# Sheet2.net
KiCad netlist of a schematic drawn in Altium Designer
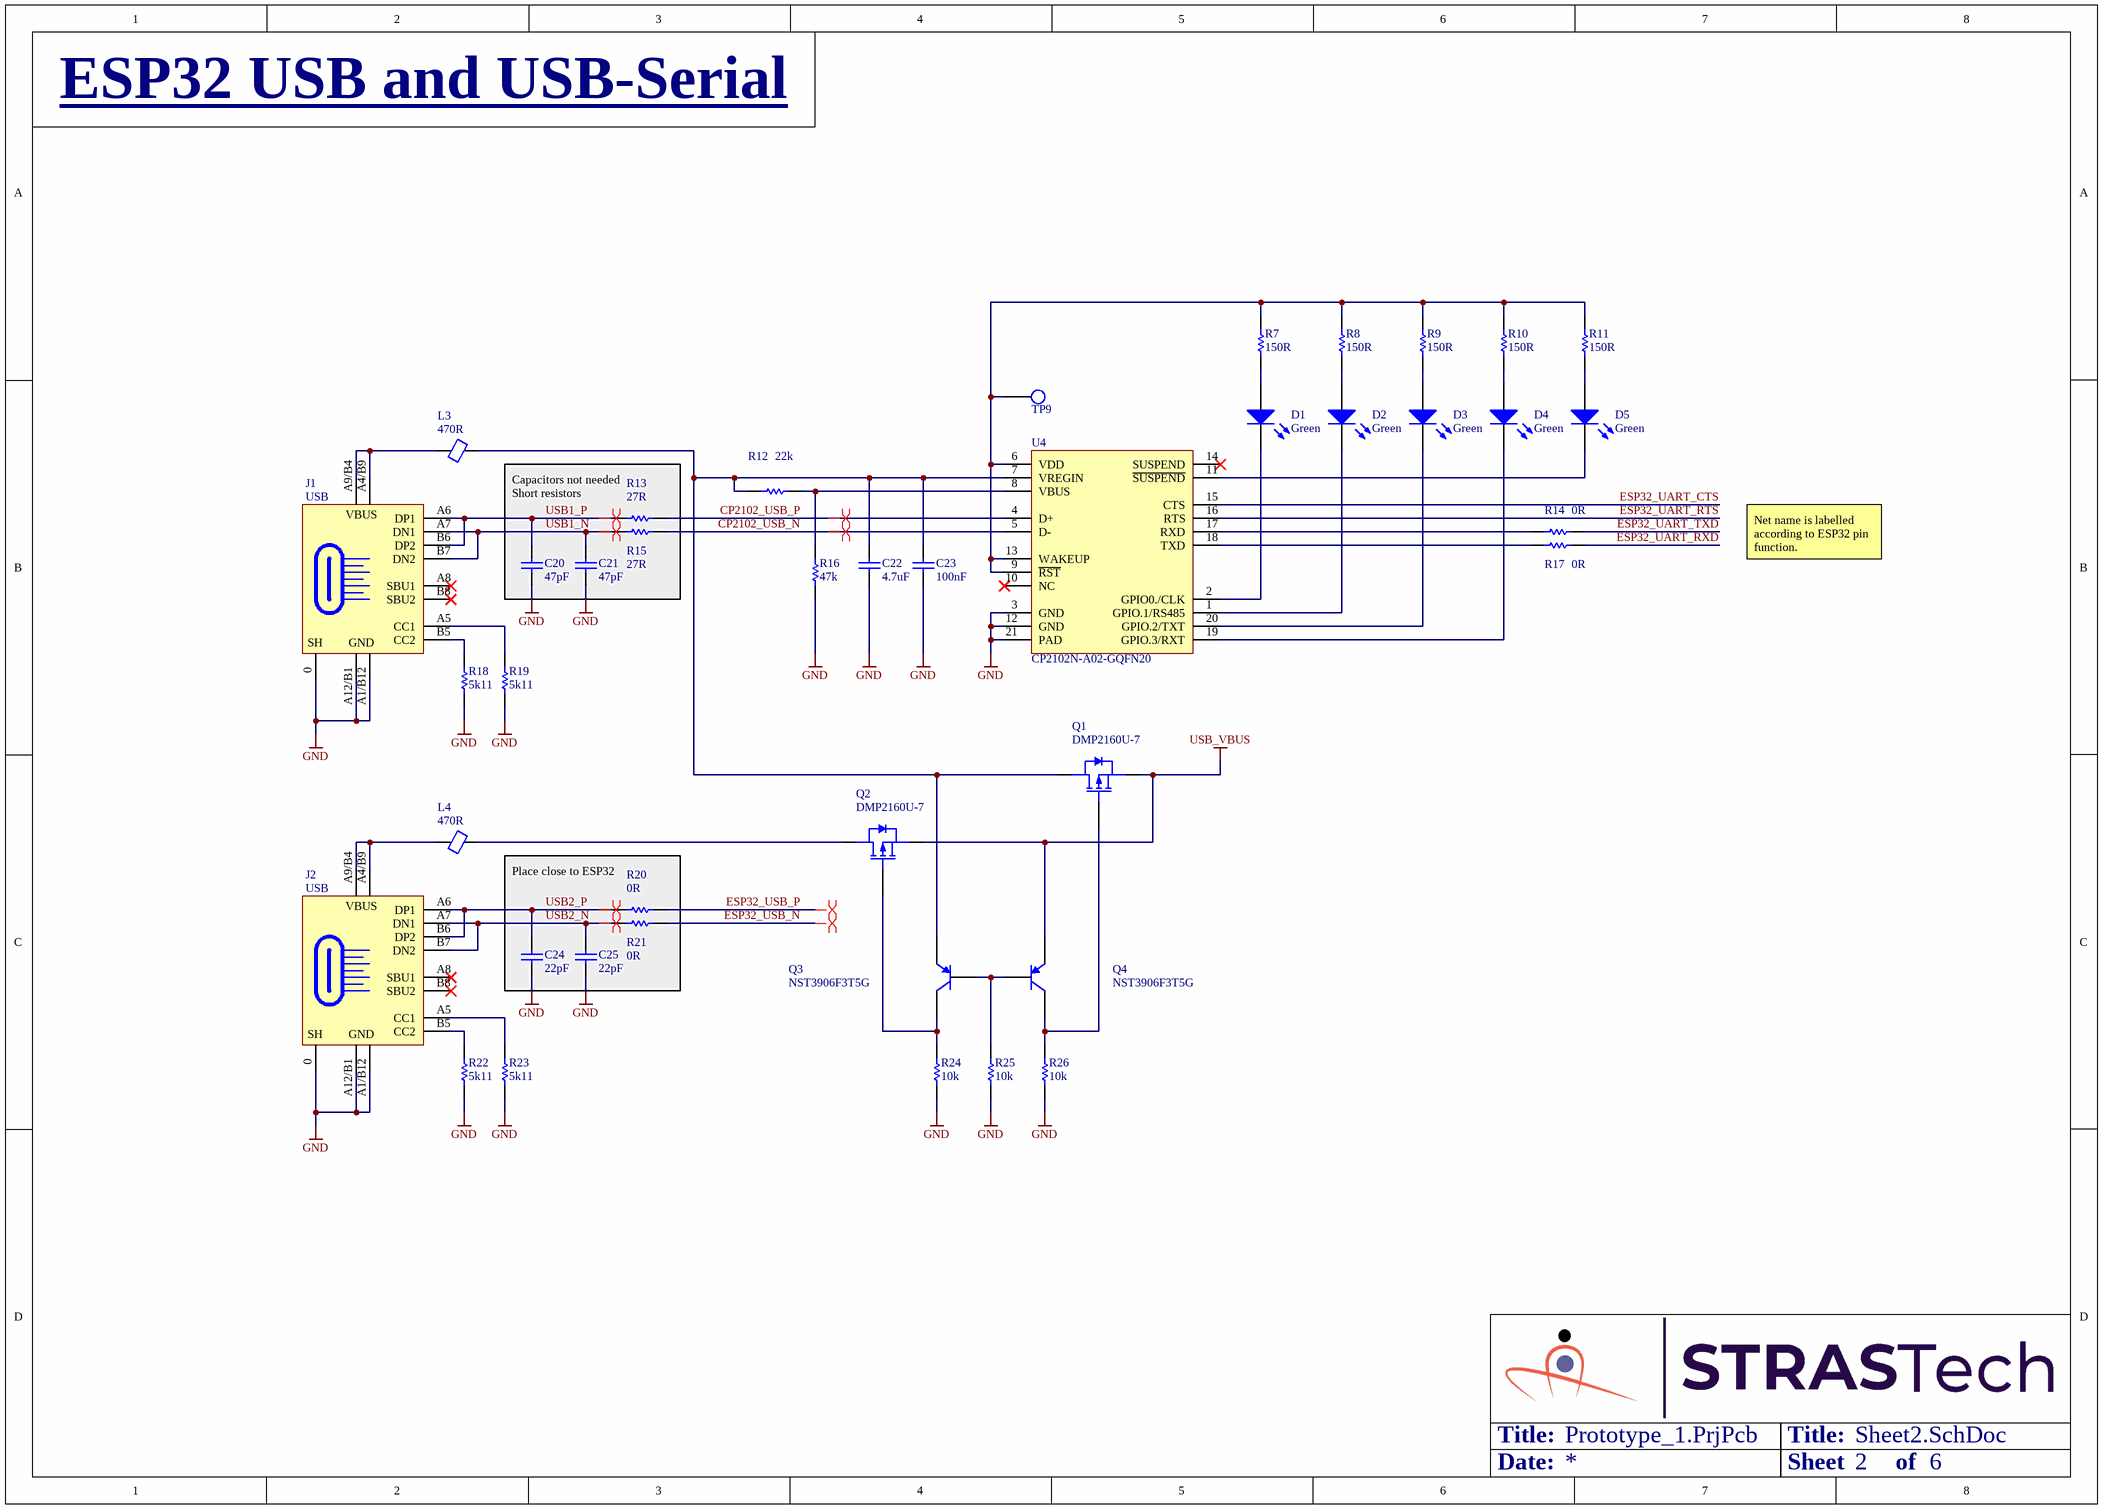
[diagram p0: Sheet2.SchDoc]

(export (version "E")
  (design (tool "Eeschema 10.0.6"))
  (components
    (comp (ref "C20")
      (value "47pF")
      (footprint "Cap,SMD,0402")
      (description "47pF ±5% 50V Ceramic Capacitor C0G, NP0 0402 (1005 Metric)")
      (fields
        (field (name "VENDOR PART NUMBER") "1292-1325-1-ND")
        (field (name "MANUFACTURER") "Walsin Technology Corporation")
        (field (name "CREATEDBY") "Judd Foster")
      )
      (libsource (lib "symbols") (part "CAP,Cer,47pF,50VDC,C0G/NP0,0402"))
    )
    (comp (ref "C21")
      (value "47pF")
      (footprint "Cap,SMD,0402")
      (description "47pF ±5% 50V Ceramic Capacitor C0G, NP0 0402 (1005 Metric)")
      (fields
        (field (name "VENDOR PART NUMBER") "1292-1325-1-ND")
        (field (name "MANUFACTURER") "Walsin Technology Corporation")
        (field (name "CREATEDBY") "Judd Foster")
      )
      (libsource (lib "symbols") (part "CAP,Cer,47pF,50VDC,C0G/NP0,0402"))
    )
    (comp (ref "C22")
      (value "4.7uF")
      (footprint "Cap,SMD,0402")
      (description "4.7 µF ±20% 16V Ceramic Capacitor X5R 0402 (1005 Metric)")
      (fields
        (field (name "VENDOR PART NUMBER") "478-10788-1-ND")
        (field (name "MANUFACTURER") "AVX Corporation")
        (field (name "CREATEDBY") "Judd Foster")
      )
      (libsource (lib "symbols") (part "CAP,Cer,4.7uF,16VDC,X5R,0402"))
    )
    (comp (ref "C23")
      (value "100nF")
      (footprint "Cap,SMD,0402")
      (description "0.1µF ±10% 25V Ceramic Capacitor X7R 0402 (1005 Metric)")
      (fields
        (field (name "VENDOR PART NUMBER") "490-14603-1-ND")
        (field (name "MANUFACTURER") "Murata Electronics")
        (field (name "CREATEDBY") "Judd Foster")
      )
      (libsource (lib "symbols") (part "CAP,Cer,100nF,25VDC,X7R,0402"))
    )
    (comp (ref "C24")
      (value "22pF")
      (footprint "Cap,SMD,0402")
      (description "22pF ±5% 25V Ceramic Capacitor C0G, NP0 0402 (1005 Metric)")
      (fields
        (field (name "VENDOR PART NUMBER") "1292-1282-1-ND")
        (field (name "MANUFACTURER") "Walsin Technology Corporation")
        (field (name "CREATEDBY") "Judd Foster")
      )
      (libsource (lib "symbols") (part "CAP,Cer,22pF,25VDC,C0G/NP0,0402"))
    )
    (comp (ref "C25")
      (value "22pF")
      (footprint "Cap,SMD,0402")
      (description "22pF ±5% 25V Ceramic Capacitor C0G, NP0 0402 (1005 Metric)")
      (fields
        (field (name "VENDOR PART NUMBER") "1292-1282-1-ND")
        (field (name "MANUFACTURER") "Walsin Technology Corporation")
        (field (name "CREATEDBY") "Judd Foster")
      )
      (libsource (lib "symbols") (part "CAP,Cer,22pF,25VDC,C0G/NP0,0402"))
    )
    (comp (ref "D1")
      (value "Green")
      (footprint "LED,0603")
      (description "Green 530nm LED Indication - Discrete 3V 0603 (1608 Metric)")
      (fields
        (field (name "MANUFACTURER") "Stanley Electric Co")
        (field (name "MANUFACTURER PART NUMBER") "THG1111C-0005-TR")
        (field (name "CREATEDBY") "Judd Foster")
      )
      (libsource (lib "symbols") (part "LED,Green,SMD,0603"))
    )
    (comp (ref "D2")
      (value "Green")
      (footprint "LED,0603")
      (description "Green 530nm LED Indication - Discrete 3V 0603 (1608 Metric)")
      (fields
        (field (name "MANUFACTURER") "Stanley Electric Co")
        (field (name "MANUFACTURER PART NUMBER") "THG1111C-0005-TR")
        (field (name "CREATEDBY") "Judd Foster")
      )
      (libsource (lib "symbols") (part "LED,Green,SMD,0603"))
    )
    (comp (ref "D3")
      (value "Green")
      (footprint "LED,0603")
      (description "Green 530nm LED Indication - Discrete 3V 0603 (1608 Metric)")
      (fields
        (field (name "MANUFACTURER") "Stanley Electric Co")
        (field (name "MANUFACTURER PART NUMBER") "THG1111C-0005-TR")
        (field (name "CREATEDBY") "Judd Foster")
      )
      (libsource (lib "symbols") (part "LED,Green,SMD,0603"))
    )
    (comp (ref "D4")
      (value "Green")
      (footprint "LED,0603")
      (description "Green 530nm LED Indication - Discrete 3V 0603 (1608 Metric)")
      (fields
        (field (name "MANUFACTURER") "Stanley Electric Co")
        (field (name "MANUFACTURER PART NUMBER") "THG1111C-0005-TR")
        (field (name "CREATEDBY") "Judd Foster")
      )
      (libsource (lib "symbols") (part "LED,Green,SMD,0603"))
    )
    (comp (ref "D5")
      (value "Green")
      (footprint "LED,0603")
      (description "Green 530nm LED Indication - Discrete 3V 0603 (1608 Metric)")
      (fields
        (field (name "MANUFACTURER") "Stanley Electric Co")
        (field (name "MANUFACTURER PART NUMBER") "THG1111C-0005-TR")
        (field (name "CREATEDBY") "Judd Foster")
      )
      (libsource (lib "symbols") (part "LED,Green,SMD,0603"))
    )
    (comp (ref "J1")
      (value "USB")
      (footprint "CONN,USB_C,SMD")
      (fields
        (field (name "MANUFACTURER") "GCT")
        (field (name "MANUFACTURER PART NUMBER") "USB4110-GF-A")
        (field (name "VENDOR PART NUMBER") "2073-USB4110-GF-A-1-ND")
        (field (name "CREATEDBY") "Judd Foster")
      )
      (libsource (lib "symbols") (part "Conn,USB_C,SMD"))
    )
    (comp (ref "J2")
      (value "USB")
      (footprint "CONN,USB_C,SMD")
      (fields
        (field (name "MANUFACTURER") "GCT")
        (field (name "MANUFACTURER PART NUMBER") "USB4110-GF-A")
        (field (name "VENDOR PART NUMBER") "2073-USB4110-GF-A-1-ND")
        (field (name "CREATEDBY") "Judd Foster")
      )
      (libsource (lib "symbols") (part "Conn,USB_C,SMD"))
    )
    (comp (ref "L3")
      (value "470R")
      (footprint "IND,0402")
      (description "470 Ohms @ 100 MHz 1 Power Line Ferrite Bead 0402 (1005 Metric) 1A 200mOhm")
      (fields
        (field (name "VENDOR PART NUMBER") "490-10662-1-ND")
        (field (name "MANUFACTURER") "Murata Electronics")
        (field (name "CREATEDBY") "Judd Foster")
      )
      (libsource (lib "symbols") (part "Ferrite,470R@100MHz,0402"))
    )
    (comp (ref "L4")
      (value "470R")
      (footprint "IND,0402")
      (description "470 Ohms @ 100 MHz 1 Power Line Ferrite Bead 0402 (1005 Metric) 1A 200mOhm")
      (fields
        (field (name "VENDOR PART NUMBER") "490-10662-1-ND")
        (field (name "MANUFACTURER") "Murata Electronics")
        (field (name "CREATEDBY") "Judd Foster")
      )
      (libsource (lib "symbols") (part "Ferrite,470R@100MHz,0402"))
    )
    (comp (ref "Q1")
      (value "DMP2160U-7")
      (footprint "SOT23-3")
      (description "P-Channel 20 V 3.2A (Ta) 1.4W (Ta) Surface Mount SOT-23-3")
      (fields
        (field (name "MANUFACTURER") "Diodes Incorporated")
        (field (name "VENDOR PART NUMBER") "DMP2160UDICT-ND")
        (field (name "CREATEDBY") "Judd Foster")
      )
      (libsource (lib "symbols") (part "MOSFET,P Ch,20V,3.2A"))
    )
    (comp (ref "Q2")
      (value "DMP2160U-7")
      (footprint "SOT23-3")
      (description "P-Channel 20 V 3.2A (Ta) 1.4W (Ta) Surface Mount SOT-23-3")
      (fields
        (field (name "MANUFACTURER") "Diodes Incorporated")
        (field (name "VENDOR PART NUMBER") "DMP2160UDICT-ND")
        (field (name "CREATEDBY") "Judd Foster")
      )
      (libsource (lib "symbols") (part "MOSFET,P Ch,20V,3.2A"))
    )
    (comp (ref "Q3")
      (value "NST3906F3T5G")
      (footprint "SOT1123")
      (description "Bipolar (BJT) Transistor PNP 40 V 200 mA 250MHz 290 mW Surface Mount SOT-1123")
      (fields
        (field (name "MANUFACTURER") "ON Semiconductor")
        (field (name "VENDOR PART NUMBER") "NST3906F3T5GOSCT-ND")
        (field (name "CREATEDBY") "Judd Foster")
      )
      (libsource (lib "symbols") (part "Trans,PNP,40V,200mA,SOT1123"))
    )
    (comp (ref "Q4")
      (value "NST3906F3T5G")
      (footprint "SOT1123")
      (description "Bipolar (BJT) Transistor PNP 40 V 200 mA 250MHz 290 mW Surface Mount SOT-1123")
      (fields
        (field (name "MANUFACTURER") "ON Semiconductor")
        (field (name "VENDOR PART NUMBER") "NST3906F3T5GOSCT-ND")
        (field (name "CREATEDBY") "Judd Foster")
      )
      (libsource (lib "symbols") (part "Trans,PNP,40V,200mA,SOT1123"))
    )
    (comp (ref "R7")
      (value "150R")
      (footprint "RES,0402")
      (fields
        (field (name "MANUFACTURER") "TE Connectivity Passive Product")
        (field (name "MANUFACTURER PART NUMBER") "CRGCQ0402F150R")
        (field (name "VENDOR PART NUMBER") "A129617CT-ND")
        (field (name "CREATEDBY") "Judd Foster")
      )
      (libsource (lib "symbols") (part "RES,150R,1%,0.1W,0402"))
    )
    (comp (ref "R8")
      (value "150R")
      (footprint "RES,0402")
      (fields
        (field (name "MANUFACTURER") "TE Connectivity Passive Product")
        (field (name "MANUFACTURER PART NUMBER") "CRGCQ0402F150R")
        (field (name "VENDOR PART NUMBER") "A129617CT-ND")
        (field (name "CREATEDBY") "Judd Foster")
      )
      (libsource (lib "symbols") (part "RES,150R,1%,0.1W,0402"))
    )
    (comp (ref "R9")
      (value "150R")
      (footprint "RES,0402")
      (fields
        (field (name "MANUFACTURER") "TE Connectivity Passive Product")
        (field (name "MANUFACTURER PART NUMBER") "CRGCQ0402F150R")
        (field (name "VENDOR PART NUMBER") "A129617CT-ND")
        (field (name "CREATEDBY") "Judd Foster")
      )
      (libsource (lib "symbols") (part "RES,150R,1%,0.1W,0402"))
    )
    (comp (ref "R10")
      (value "150R")
      (footprint "RES,0402")
      (fields
        (field (name "MANUFACTURER") "TE Connectivity Passive Product")
        (field (name "MANUFACTURER PART NUMBER") "CRGCQ0402F150R")
        (field (name "VENDOR PART NUMBER") "A129617CT-ND")
        (field (name "CREATEDBY") "Judd Foster")
      )
      (libsource (lib "symbols") (part "RES,150R,1%,0.1W,0402"))
    )
    (comp (ref "R11")
      (value "150R")
      (footprint "RES,0402")
      (fields
        (field (name "MANUFACTURER") "TE Connectivity Passive Product")
        (field (name "MANUFACTURER PART NUMBER") "CRGCQ0402F150R")
        (field (name "VENDOR PART NUMBER") "A129617CT-ND")
        (field (name "CREATEDBY") "Judd Foster")
      )
      (libsource (lib "symbols") (part "RES,150R,1%,0.1W,0402"))
    )
    (comp (ref "R12")
      (value "22k")
      (footprint "RES,0402")
      (description "22 kOhms ±1% 0.063W, 1/16W Chip Resistor 0402 (1005 Metric) Automotive AEC-Q200 Thick Film")
      (fields
        (field (name "VENDOR PART NUMBER") "RMCF0402FT22K0CT-ND")
        (field (name "MANUFACTURER") "Stackpole Electronics Inc")
        (field (name "CREATEDBY") "Judd Foster")
      )
      (libsource (lib "symbols") (part "RES,22k,1%,0.063W,0402"))
    )
    (comp (ref "R13")
      (value "27R")
      (footprint "RES,0402")
      (description "27 Ohms ±5% 0.063W, 1/16W Chip Resistor 0402 (1005 Metric) Automotive AEC-Q200 Thick Film")
      (fields
        (field (name "VENDOR PART NUMBER") "RMCF0402JT27R0CT-ND")
        (field (name "MANUFACTURER") "Stackpole Electronics Inc")
        (field (name "CREATEDBY") "Judd Foster")
      )
      (libsource (lib "symbols") (part "RES,27R,5%,0.063W,0402"))
    )
    (comp (ref "R14")
      (value "0R")
      (footprint "RES,0402")
      (description "0 Ohms Jumper 0.1W, 1/10W Chip Resistor 0402 (1005 Metric) Automotive AEC-Q200 Thick Film")
      (fields
        (field (name "MANUFACTURER") "Panasonic Electronic Components")
        (field (name "MANUFACTURER PART NUMBER") "ERJ-2GE0R00X")
        (field (name "CREATEDBY") "Judd Foster")
      )
      (libsource (lib "symbols") (part "RES,0R0,0.1W,0402"))
    )
    (comp (ref "R15")
      (value "27R")
      (footprint "RES,0402")
      (description "27 Ohms ±5% 0.063W, 1/16W Chip Resistor 0402 (1005 Metric) Automotive AEC-Q200 Thick Film")
      (fields
        (field (name "VENDOR PART NUMBER") "RMCF0402JT27R0CT-ND")
        (field (name "MANUFACTURER") "Stackpole Electronics Inc")
        (field (name "CREATEDBY") "Judd Foster")
      )
      (libsource (lib "symbols") (part "RES,27R,5%,0.063W,0402"))
    )
    (comp (ref "R16")
      (value "47k")
      (footprint "RES,0402")
      (description "47 kOhms ±1% 0.1W, 1/10W Chip Resistor 0402 (1005 Metric) Automotive AEC-Q200 Thick Film")
      (fields
        (field (name "MANUFACTURER") "Panasonic Electronic Components")
        (field (name "MANUFACTURER PART NUMBER") "ERJ-2RKF4702X")
        (field (name "CREATEDBY") "Judd Foster")
      )
      (libsource (lib "symbols") (part "RES,47k,1%,0.1W,0402"))
    )
    (comp (ref "R17")
      (value "0R")
      (footprint "RES,0402")
      (description "0 Ohms Jumper 0.1W, 1/10W Chip Resistor 0402 (1005 Metric) Automotive AEC-Q200 Thick Film")
      (fields
        (field (name "MANUFACTURER") "Panasonic Electronic Components")
        (field (name "MANUFACTURER PART NUMBER") "ERJ-2GE0R00X")
        (field (name "CREATEDBY") "Judd Foster")
      )
      (libsource (lib "symbols") (part "RES,0R0,0.1W,0402"))
    )
    (comp (ref "R18")
      (value "5k11")
      (footprint "RES,0402")
      (fields
        (field (name "MANUFACTURER") "Yageo")
        (field (name "MANUFACTURER PART NUMBER") "AC0402FR-075K11L")
        (field (name "VENDOR PART NUMBER") "13-AC0402FR-075K11LCT-ND")
        (field (name "CREATEDBY") "Judd Foster")
      )
      (libsource (lib "symbols") (part "RES,5k11,1%,0.063W,0402"))
    )
    (comp (ref "R19")
      (value "5k11")
      (footprint "RES,0402")
      (fields
        (field (name "MANUFACTURER") "Yageo")
        (field (name "MANUFACTURER PART NUMBER") "AC0402FR-075K11L")
        (field (name "VENDOR PART NUMBER") "13-AC0402FR-075K11LCT-ND")
        (field (name "CREATEDBY") "Judd Foster")
      )
      (libsource (lib "symbols") (part "RES,5k11,1%,0.063W,0402"))
    )
    (comp (ref "R20")
      (value "0R")
      (footprint "RES,0402")
      (description "0 Ohms Jumper 0.1W, 1/10W Chip Resistor 0402 (1005 Metric) Automotive AEC-Q200 Thick Film")
      (fields
        (field (name "MANUFACTURER") "Panasonic Electronic Components")
        (field (name "MANUFACTURER PART NUMBER") "ERJ-2GE0R00X")
        (field (name "CREATEDBY") "Judd Foster")
      )
      (libsource (lib "symbols") (part "RES,0R0,0.1W,0402"))
    )
    (comp (ref "R21")
      (value "0R")
      (footprint "RES,0402")
      (description "0 Ohms Jumper 0.1W, 1/10W Chip Resistor 0402 (1005 Metric) Automotive AEC-Q200 Thick Film")
      (fields
        (field (name "MANUFACTURER") "Panasonic Electronic Components")
        (field (name "MANUFACTURER PART NUMBER") "ERJ-2GE0R00X")
        (field (name "CREATEDBY") "Judd Foster")
      )
      (libsource (lib "symbols") (part "RES,0R0,0.1W,0402"))
    )
    (comp (ref "R22")
      (value "5k11")
      (footprint "RES,0402")
      (fields
        (field (name "MANUFACTURER") "Yageo")
        (field (name "MANUFACTURER PART NUMBER") "AC0402FR-075K11L")
        (field (name "VENDOR PART NUMBER") "13-AC0402FR-075K11LCT-ND")
        (field (name "CREATEDBY") "Judd Foster")
      )
      (libsource (lib "symbols") (part "RES,5k11,1%,0.063W,0402"))
    )
    (comp (ref "R23")
      (value "5k11")
      (footprint "RES,0402")
      (fields
        (field (name "MANUFACTURER") "Yageo")
        (field (name "MANUFACTURER PART NUMBER") "AC0402FR-075K11L")
        (field (name "VENDOR PART NUMBER") "13-AC0402FR-075K11LCT-ND")
        (field (name "CREATEDBY") "Judd Foster")
      )
      (libsource (lib "symbols") (part "RES,5k11,1%,0.063W,0402"))
    )
    (comp (ref "R24")
      (value "10k")
      (footprint "RES,0402")
      (description "10 kOhms ±5% 0.063W, 1/16W Chip Resistor 0402 (1005 Metric) Automotive AEC-Q200 Thick Film")
      (fields
        (field (name "VENDOR PART NUMBER") "RMCF0402JT10K0CT-ND")
        (field (name "MANUFACTURER") "Stackpole Electronics Inc")
        (field (name "CREATEDBY") "Judd Foster")
      )
      (libsource (lib "symbols") (part "RES,10k,5%,0.063W,0402"))
    )
    (comp (ref "R25")
      (value "10k")
      (footprint "RES,0402")
      (description "10 kOhms ±5% 0.063W, 1/16W Chip Resistor 0402 (1005 Metric) Automotive AEC-Q200 Thick Film")
      (fields
        (field (name "VENDOR PART NUMBER") "RMCF0402JT10K0CT-ND")
        (field (name "MANUFACTURER") "Stackpole Electronics Inc")
        (field (name "CREATEDBY") "Judd Foster")
      )
      (libsource (lib "symbols") (part "RES,10k,5%,0.063W,0402"))
    )
    (comp (ref "R26")
      (value "10k")
      (footprint "RES,0402")
      (description "10 kOhms ±5% 0.063W, 1/16W Chip Resistor 0402 (1005 Metric) Automotive AEC-Q200 Thick Film")
      (fields
        (field (name "VENDOR PART NUMBER") "RMCF0402JT10K0CT-ND")
        (field (name "MANUFACTURER") "Stackpole Electronics Inc")
        (field (name "CREATEDBY") "Judd Foster")
      )
      (libsource (lib "symbols") (part "RES,10k,5%,0.063W,0402"))
    )
    (comp (ref "TP9")
      (value "TESTPOINT")
      (footprint "testpoint,smd,round,1mm")
      (description "PCB Testpoint")
      (fields (field (name "CREATEDBY") "Judd Foster"))
      (libsource (lib "symbols") (part "TESTPOINT"))
    )
    (comp (ref "U4")
      (value "CP2102N-A02-GQFN20")
      (footprint "IC,QFN-20,3x3,PAD")
      (description "USB Bridge, USB to UART USB 2.0 UART Interface 20-QFN (3x3)")
      (fields
        (field (name "MANUFACTURER") "Silicon Labs")
        (field (name "VENDOR PART NUMBER") "336-5885-ND")
        (field (name "CREATEDBY") "Judd Foster")
      )
      (libsource (lib "symbols") (part "CP2102N-A02-GQFN20"))
    )
  )
  (nets
    (net (code "1") (name "/CP2102_USB_N") (class "Default")
      (node (ref "R15") (pin "2") (pinfunction "2_2") (pintype "passive"))
      (node (ref "U4") (pin "5") (pinfunction "D-_5") (pintype "passive"))
    )
    (net (code "2") (name "/CP2102_USB_P") (class "Default")
      (node (ref "R13") (pin "2") (pinfunction "2_2") (pintype "passive"))
      (node (ref "U4") (pin "4") (pinfunction "D+_4") (pintype "passive"))
    )
    (net (code "3") (name "/ESP32_UART_CTS") (class "Default")
      (node (ref "U4") (pin "15") (pinfunction "CTS_15") (pintype "passive"))
    )
    (net (code "4") (name "/ESP32_UART_RTS") (class "Default")
      (node (ref "U4") (pin "16") (pinfunction "RTS_16") (pintype "passive"))
    )
    (net (code "5") (name "/ESP32_UART_RXD") (class "Default")
      (node (ref "R17") (pin "2") (pinfunction "2_2") (pintype "passive"))
    )
    (net (code "6") (name "/ESP32_UART_TXD") (class "Default")
      (node (ref "R14") (pin "2") (pinfunction "2_2") (pintype "passive"))
    )
    (net (code "7") (name "/ESP32_USB_N") (class "Default")
      (node (ref "R21") (pin "2") (pinfunction "2_2") (pintype "passive"))
    )
    (net (code "8") (name "/ESP32_USB_P") (class "Default")
      (node (ref "R20") (pin "2") (pinfunction "2_2") (pintype "passive"))
    )
    (net (code "9") (name "/USB1_N") (class "Default")
      (node (ref "C21") (pin "2") (pinfunction "2_2") (pintype "passive"))
      (node (ref "J1") (pin "A7") (pinfunction "DN1_A7") (pintype "passive"))
      (node (ref "J1") (pin "B7") (pinfunction "DN2_B7") (pintype "passive"))
      (node (ref "R15") (pin "1") (pinfunction "1_1") (pintype "passive"))
    )
    (net (code "10") (name "/USB1_P") (class "Default")
      (node (ref "C20") (pin "2") (pinfunction "2_2") (pintype "passive"))
      (node (ref "J1") (pin "A6") (pinfunction "DP1_A6") (pintype "passive"))
      (node (ref "J1") (pin "B6") (pinfunction "DP2_B6") (pintype "passive"))
      (node (ref "R13") (pin "1") (pinfunction "1_1") (pintype "passive"))
    )
    (net (code "11") (name "/USB2_N") (class "Default")
      (node (ref "C25") (pin "2") (pinfunction "2_2") (pintype "passive"))
      (node (ref "J2") (pin "A7") (pinfunction "DN1_A7") (pintype "passive"))
      (node (ref "J2") (pin "B7") (pinfunction "DN2_B7") (pintype "passive"))
      (node (ref "R21") (pin "1") (pinfunction "1_1") (pintype "passive"))
    )
    (net (code "12") (name "/USB2_P") (class "Default")
      (node (ref "C24") (pin "2") (pinfunction "2_2") (pintype "passive"))
      (node (ref "J2") (pin "A6") (pinfunction "DP1_A6") (pintype "passive"))
      (node (ref "J2") (pin "B6") (pinfunction "DP2_B6") (pintype "passive"))
      (node (ref "R20") (pin "1") (pinfunction "1_1") (pintype "passive"))
    )
    (net (code "13") (name "GND") (class "Default")
      (node (ref "C20") (pin "1") (pinfunction "1_1") (pintype "passive"))
      (node (ref "C21") (pin "1") (pinfunction "1_1") (pintype "passive"))
      (node (ref "C22") (pin "1") (pinfunction "1_1") (pintype "passive"))
      (node (ref "C23") (pin "1") (pinfunction "1_1") (pintype "passive"))
      (node (ref "C24") (pin "1") (pinfunction "1_1") (pintype "passive"))
      (node (ref "C25") (pin "1") (pinfunction "1_1") (pintype "passive"))
      (node (ref "J1") (pin "0") (pinfunction "SHIELD_0") (pintype "passive"))
      (node (ref "J1") (pin "A1/B12") (pinfunction "GND_A1/B12") (pintype "passive"))
      (node (ref "J1") (pin "A12/B1") (pinfunction "GND_A12/B1") (pintype "passive"))
      (node (ref "J2") (pin "0") (pinfunction "SHIELD_0") (pintype "passive"))
      (node (ref "J2") (pin "A1/B12") (pinfunction "GND_A1/B12") (pintype "passive"))
      (node (ref "J2") (pin "A12/B1") (pinfunction "GND_A12/B1") (pintype "passive"))
      (node (ref "R16") (pin "1") (pinfunction "1_1") (pintype "passive"))
      (node (ref "R18") (pin "1") (pinfunction "1_1") (pintype "passive"))
      (node (ref "R19") (pin "1") (pinfunction "1_1") (pintype "passive"))
      (node (ref "R22") (pin "1") (pinfunction "1_1") (pintype "passive"))
      (node (ref "R23") (pin "1") (pinfunction "1_1") (pintype "passive"))
      (node (ref "R24") (pin "2") (pinfunction "2_2") (pintype "passive"))
      (node (ref "R25") (pin "2") (pinfunction "2_2") (pintype "passive"))
      (node (ref "R26") (pin "2") (pinfunction "2_2") (pintype "passive"))
      (node (ref "U4") (pin "12") (pinfunction "GND_12") (pintype "passive"))
      (node (ref "U4") (pin "21") (pinfunction "PAD_21") (pintype "passive"))
      (node (ref "U4") (pin "3") (pinfunction "GND_3") (pintype "passive"))
    )
    (net (code "14") (name "Net-(D1-A)") (class "Default")
      (node (ref "D1") (pin "1") (pinfunction "A_1") (pintype "passive"))
      (node (ref "R7") (pin "1") (pinfunction "1_1") (pintype "passive"))
    )
    (net (code "15") (name "Net-(D1-K)") (class "Default")
      (node (ref "D1") (pin "2") (pinfunction "K_2") (pintype "passive"))
      (node (ref "U4") (pin "2") (pinfunction "GPIO0./CLK_2") (pintype "passive"))
    )
    (net (code "16") (name "Net-(D2-A)") (class "Default")
      (node (ref "D2") (pin "1") (pinfunction "A_1") (pintype "passive"))
      (node (ref "R8") (pin "1") (pinfunction "1_1") (pintype "passive"))
    )
    (net (code "17") (name "Net-(D2-K)") (class "Default")
      (node (ref "D2") (pin "2") (pinfunction "K_2") (pintype "passive"))
      (node (ref "U4") (pin "1") (pinfunction "GPIO.1/RS485_1") (pintype "passive"))
    )
    (net (code "18") (name "Net-(D3-A)") (class "Default")
      (node (ref "D3") (pin "1") (pinfunction "A_1") (pintype "passive"))
      (node (ref "R9") (pin "1") (pinfunction "1_1") (pintype "passive"))
    )
    (net (code "19") (name "Net-(D3-K)") (class "Default")
      (node (ref "D3") (pin "2") (pinfunction "K_2") (pintype "passive"))
      (node (ref "U4") (pin "20") (pinfunction "GPIO.2/TXT_20") (pintype "passive"))
    )
    (net (code "20") (name "Net-(D4-A)") (class "Default")
      (node (ref "D4") (pin "1") (pinfunction "A_1") (pintype "passive"))
      (node (ref "R10") (pin "1") (pinfunction "1_1") (pintype "passive"))
    )
    (net (code "21") (name "Net-(D4-K)") (class "Default")
      (node (ref "D4") (pin "2") (pinfunction "K_2") (pintype "passive"))
      (node (ref "U4") (pin "19") (pinfunction "GPIO.3/RXT_19") (pintype "passive"))
    )
    (net (code "22") (name "Net-(D5-A)") (class "Default")
      (node (ref "D5") (pin "1") (pinfunction "A_1") (pintype "passive"))
      (node (ref "R11") (pin "1") (pinfunction "1_1") (pintype "passive"))
    )
    (net (code "23") (name "Net-(D5-K)") (class "Default")
      (node (ref "D5") (pin "2") (pinfunction "K_2") (pintype "passive"))
      (node (ref "U4") (pin "11") (pinfunction "~{SUSPEND}_11") (pintype "passive"))
    )
    (net (code "24") (name "Net-(J1-CC1)") (class "Default")
      (node (ref "J1") (pin "A5") (pinfunction "CC1_A5") (pintype "passive"))
      (node (ref "R19") (pin "2") (pinfunction "2_2") (pintype "passive"))
    )
    (net (code "25") (name "Net-(J1-CC2)") (class "Default")
      (node (ref "J1") (pin "B5") (pinfunction "CC2_B5") (pintype "passive"))
      (node (ref "R18") (pin "2") (pinfunction "2_2") (pintype "passive"))
    )
    (net (code "26") (name "Net-(J1-VBUS-PadA4{slash}B9)") (class "Default")
      (node (ref "J1") (pin "A4/B9") (pinfunction "VBUS_A4/B9") (pintype "passive"))
      (node (ref "J1") (pin "A9/B4") (pinfunction "VBUS_A9/B4") (pintype "passive"))
      (node (ref "L3") (pin "1") (pinfunction "1_1") (pintype "passive"))
    )
    (net (code "27") (name "Net-(J2-CC1)") (class "Default")
      (node (ref "J2") (pin "A5") (pinfunction "CC1_A5") (pintype "passive"))
      (node (ref "R23") (pin "2") (pinfunction "2_2") (pintype "passive"))
    )
    (net (code "28") (name "Net-(J2-CC2)") (class "Default")
      (node (ref "J2") (pin "B5") (pinfunction "CC2_B5") (pintype "passive"))
      (node (ref "R22") (pin "2") (pinfunction "2_2") (pintype "passive"))
    )
    (net (code "29") (name "Net-(J2-VBUS-PadA4{slash}B9)") (class "Default")
      (node (ref "J2") (pin "A4/B9") (pinfunction "VBUS_A4/B9") (pintype "passive"))
      (node (ref "J2") (pin "A9/B4") (pinfunction "VBUS_A9/B4") (pintype "passive"))
      (node (ref "L4") (pin "1") (pinfunction "1_1") (pintype "passive"))
    )
    (net (code "30") (name "Net-(Q1-D)") (class "Default")
      (node (ref "C22") (pin "2") (pinfunction "2_2") (pintype "passive"))
      (node (ref "C23") (pin "2") (pinfunction "2_2") (pintype "passive"))
      (node (ref "L3") (pin "2") (pinfunction "2_2") (pintype "passive"))
      (node (ref "Q1") (pin "3") (pinfunction "D_3") (pintype "passive"))
      (node (ref "Q3") (pin "2") (pinfunction "E_2") (pintype "passive"))
      (node (ref "R12") (pin "1") (pinfunction "1_1") (pintype "passive"))
      (node (ref "U4") (pin "7") (pinfunction "VREGIN_7") (pintype "passive"))
    )
    (net (code "31") (name "Net-(Q1-G)") (class "Default")
      (node (ref "Q1") (pin "1") (pinfunction "G_1") (pintype "passive"))
      (node (ref "Q4") (pin "3") (pinfunction "C_3") (pintype "passive"))
      (node (ref "R26") (pin "1") (pinfunction "1_1") (pintype "passive"))
    )
    (net (code "32") (name "Net-(Q2-D)") (class "Default")
      (node (ref "L4") (pin "2") (pinfunction "2_2") (pintype "passive"))
      (node (ref "Q2") (pin "3") (pinfunction "D_3") (pintype "passive"))
    )
    (net (code "33") (name "Net-(Q2-G)") (class "Default")
      (node (ref "Q2") (pin "1") (pinfunction "G_1") (pintype "passive"))
      (node (ref "Q3") (pin "3") (pinfunction "C_3") (pintype "passive"))
      (node (ref "R24") (pin "1") (pinfunction "1_1") (pintype "passive"))
    )
    (net (code "34") (name "Net-(Q3-B)") (class "Default")
      (node (ref "Q3") (pin "1") (pinfunction "B_1") (pintype "passive"))
      (node (ref "Q4") (pin "1") (pinfunction "B_1") (pintype "passive"))
      (node (ref "R25") (pin "1") (pinfunction "1_1") (pintype "passive"))
    )
    (net (code "35") (name "Net-(TP9-TP)") (class "Default")
      (node (ref "R10") (pin "2") (pinfunction "2_2") (pintype "passive"))
      (node (ref "R11") (pin "2") (pinfunction "2_2") (pintype "passive"))
      (node (ref "R7") (pin "2") (pinfunction "2_2") (pintype "passive"))
      (node (ref "R8") (pin "2") (pinfunction "2_2") (pintype "passive"))
      (node (ref "R9") (pin "2") (pinfunction "2_2") (pintype "passive"))
      (node (ref "TP9") (pin "1") (pinfunction "TP_1") (pintype "passive"))
      (node (ref "U4") (pin "13") (pinfunction "WAKEUP_13") (pintype "passive"))
      (node (ref "U4") (pin "6") (pinfunction "VDD_6") (pintype "passive"))
      (node (ref "U4") (pin "9") (pinfunction "~{RST}_9") (pintype "passive"))
    )
    (net (code "36") (name "Net-(U4-RXD)") (class "Default")
      (node (ref "R14") (pin "1") (pinfunction "1_1") (pintype "passive"))
      (node (ref "U4") (pin "17") (pinfunction "RXD_17") (pintype "passive"))
    )
    (net (code "37") (name "Net-(U4-TXD)") (class "Default")
      (node (ref "R17") (pin "1") (pinfunction "1_1") (pintype "passive"))
      (node (ref "U4") (pin "18") (pinfunction "TXD_18") (pintype "passive"))
    )
    (net (code "38") (name "Net-(U4-VBUS)") (class "Default")
      (node (ref "R12") (pin "2") (pinfunction "2_2") (pintype "passive"))
      (node (ref "R16") (pin "2") (pinfunction "2_2") (pintype "passive"))
      (node (ref "U4") (pin "8") (pinfunction "VBUS_8") (pintype "passive"))
    )
    (net (code "39") (name "USB_VBUS") (class "Default")
      (node (ref "Q1") (pin "2") (pinfunction "S_2") (pintype "passive"))
      (node (ref "Q2") (pin "2") (pinfunction "S_2") (pintype "passive"))
      (node (ref "Q4") (pin "2") (pinfunction "E_2") (pintype "passive"))
    )
    (net (code "40") (name "unconnected-(J1-SBU1-PadA8)") (class "Default")
      (node (ref "J1") (pin "A8") (pinfunction "SBU1_A8") (pintype "passive+no_connect"))
    )
    (net (code "41") (name "unconnected-(J1-SBU2-PadB8)") (class "Default")
      (node (ref "J1") (pin "B8") (pinfunction "SBU2_B8") (pintype "passive+no_connect"))
    )
    (net (code "42") (name "unconnected-(J2-SBU1-PadA8)") (class "Default")
      (node (ref "J2") (pin "A8") (pinfunction "SBU1_A8") (pintype "passive+no_connect"))
    )
    (net (code "43") (name "unconnected-(J2-SBU2-PadB8)") (class "Default")
      (node (ref "J2") (pin "B8") (pinfunction "SBU2_B8") (pintype "passive+no_connect"))
    )
    (net (code "44") (name "unconnected-(U4-NC-Pad10)") (class "Default")
      (node (ref "U4") (pin "10") (pinfunction "NC_10") (pintype "passive+no_connect"))
    )
    (net (code "45") (name "unconnected-(U4-SUSPEND-Pad14)") (class "Default")
      (node (ref "U4") (pin "14") (pinfunction "SUSPEND_14") (pintype "passive+no_connect"))
    )
  )
)
